# microcontroller.net
KiCad netlist of a schematic drawn in Altium Designer
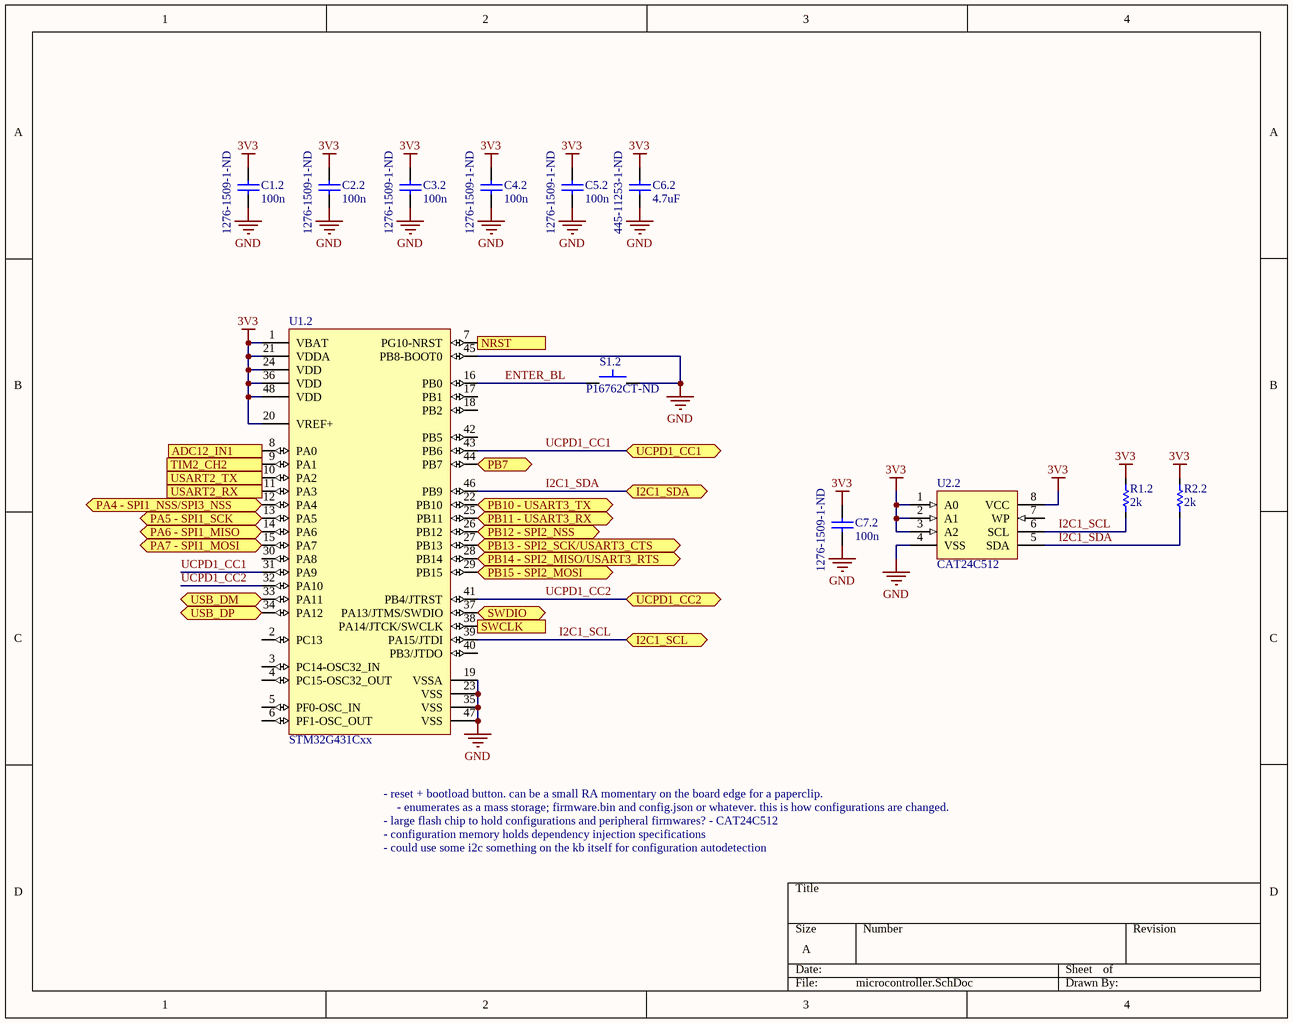
[diagram p0: microcontroller.SchDoc]

(export (version "E")
  (design (tool "Eeschema 10.0.6"))
  (components
    (comp (ref "C1.2")
      (value "100n")
      (footprint "0402")
      (fields (field (name "SUPPLIER PART NUMBER 1") "1276-1509-1-ND"))
      (libsource (lib "Luminaire") (part "CAPACITOR NON_POL"))
    )
    (comp (ref "C2.2")
      (value "100n")
      (footprint "0402")
      (fields (field (name "SUPPLIER PART NUMBER 1") "1276-1509-1-ND"))
      (libsource (lib "Luminaire") (part "CAPACITOR NON_POL"))
    )
    (comp (ref "C3.2")
      (value "100n")
      (footprint "0402")
      (fields (field (name "SUPPLIER PART NUMBER 1") "1276-1509-1-ND"))
      (libsource (lib "Luminaire") (part "CAPACITOR NON_POL"))
    )
    (comp (ref "C4.2")
      (value "100n")
      (footprint "0402")
      (fields (field (name "SUPPLIER PART NUMBER 1") "1276-1509-1-ND"))
      (libsource (lib "Luminaire") (part "CAPACITOR NON_POL"))
    )
    (comp (ref "C5.2")
      (value "100n")
      (footprint "0402")
      (fields (field (name "SUPPLIER PART NUMBER 1") "1276-1509-1-ND"))
      (libsource (lib "Luminaire") (part "CAPACITOR NON_POL"))
    )
    (comp (ref "C6.2")
      (value "4.7uF")
      (footprint "1608[0603]")
      (fields (field (name "SUPPLIER PART NUMBER 1") "445-11253-1-ND"))
      (libsource (lib "KEMET Chip Capacitor") (part "C0402"))
    )
    (comp (ref "C7.2")
      (value "100n")
      (footprint "0402")
      (fields (field (name "SUPPLIER PART NUMBER 1") "1276-1509-1-ND"))
      (libsource (lib "Luminaire") (part "CAPACITOR NON_POL"))
    )
    (comp (ref "R1.2")
      (value "2k")
      (footprint "0402")
      (fields
        (field (name "MANUFACTURER") "Yageo")
        (field (name "MANUFACTURER PART NUMBER") "RC0402JR-072KL")
        (field (name "TOLERANCE") "±5%")
      )
      (libsource (lib "Luminaire") (part "RESISTOR"))
    )
    (comp (ref "R2.2")
      (value "2k")
      (footprint "0402")
      (fields
        (field (name "MANUFACTURER") "Yageo")
        (field (name "MANUFACTURER PART NUMBER") "RC0402JR-072KL")
        (field (name "TOLERANCE") "±5%")
      )
      (libsource (lib "Luminaire") (part "RESISTOR"))
    )
    (comp (ref "S1.2")
      (value "MOM_SWITCH")
      (footprint "EVQ-P6D/P")
      (description "Momentary switch")
      (fields (field (name "SUPPLIER PART NUMBER 1") "P16762CT-ND"))
      (libsource (lib "pokey") (part "MOM_SWITCH"))
    )
    (comp (ref "U1.2")
      (value "STM32G431Cxx")
      (footprint "TSQFP50P900X900X160-48N")
      (libsource (lib "pokey") (part "STM32G431Cxx"))
    )
    (comp (ref "U2.2")
      (value "CAT24C512")
      (footprint "TSOP65P640X120-8N")
      (libsource (lib "pokey") (part "CAT24C512"))
    )
  )
  (nets
    (net (code "1") (name "/ADC12_IN1") (class "Default")
      (node (ref "U1.2") (pin "8") (pinfunction "PA0_8") (pintype "bidirectional"))
    )
    (net (code "2") (name "/ENTER_BL") (class "Default")
      (node (ref "S1.2") (pin "1") (pinfunction "1_1") (pintype "passive"))
      (node (ref "U1.2") (pin "16") (pinfunction "PB0_16") (pintype "bidirectional"))
    )
    (net (code "3") (name "/I2C1_SCL") (class "Default")
      (node (ref "R1.2") (pin "1") (pinfunction "1_1") (pintype "passive"))
      (node (ref "U1.2") (pin "39") (pinfunction "PA15/JTDI_39") (pintype "bidirectional"))
      (node (ref "U2.2") (pin "6") (pinfunction "SCL_6") (pintype "open_collector"))
    )
    (net (code "4") (name "/I2C1_SDA") (class "Default")
      (node (ref "R2.2") (pin "1") (pinfunction "1_1") (pintype "passive"))
      (node (ref "U1.2") (pin "46") (pinfunction "PB9_46") (pintype "bidirectional"))
      (node (ref "U2.2") (pin "5") (pinfunction "SDA_5") (pintype "open_collector"))
    )
    (net (code "6") (name "/NRST") (class "Default")
      (node (ref "U1.2") (pin "7") (pinfunction "PG10-NRST_7") (pintype "bidirectional"))
    )
    (net (code "7") (name "/PA4 - SPI1_NSS{slash}SPI3_NSS") (class "Default")
      (node (ref "U1.2") (pin "12") (pinfunction "PA4_12") (pintype "bidirectional"))
    )
    (net (code "8") (name "/PA5 - SPI1_SCK") (class "Default")
      (node (ref "U1.2") (pin "13") (pinfunction "PA5_13") (pintype "bidirectional"))
    )
    (net (code "9") (name "/PA6 - SPI1_MISO") (class "Default")
      (node (ref "U1.2") (pin "14") (pinfunction "PA6_14") (pintype "bidirectional"))
    )
    (net (code "19") (name "/PA7 - SPI1_MOSI") (class "Default")
      (node (ref "U1.2") (pin "15") (pinfunction "PA7_15") (pintype "bidirectional"))
    )
    (net (code "20") (name "/PB7") (class "Default")
      (node (ref "U1.2") (pin "44") (pinfunction "PB7_44") (pintype "bidirectional"))
    )
    (net (code "21") (name "/PB10 - USART3_TX") (class "Default")
      (node (ref "U1.2") (pin "22") (pinfunction "PB10_22") (pintype "bidirectional"))
    )
    (net (code "22") (name "/PB11 - USART3_RX") (class "Default")
      (node (ref "U1.2") (pin "25") (pinfunction "PB11_25") (pintype "bidirectional"))
    )
    (net (code "23") (name "/PB12 - SPI2_NSS") (class "Default")
      (node (ref "U1.2") (pin "26") (pinfunction "PB12_26") (pintype "bidirectional"))
    )
    (net (code "24") (name "/PB13 - SPI2_SCK{slash}USART3_CTS") (class "Default")
      (node (ref "U1.2") (pin "27") (pinfunction "PB13_27") (pintype "bidirectional"))
    )
    (net (code "25") (name "/PB14 - SPI2_MISO{slash}USART3_RTS") (class "Default")
      (node (ref "U1.2") (pin "28") (pinfunction "PB14_28") (pintype "bidirectional"))
    )
    (net (code "26") (name "/PB15 - SPI2_MOSI") (class "Default")
      (node (ref "U1.2") (pin "29") (pinfunction "PB15_29") (pintype "bidirectional"))
    )
    (net (code "27") (name "/SWCLK") (class "Default")
      (node (ref "U1.2") (pin "38") (pinfunction "PA14/JTCK/SWCLK_38") (pintype "bidirectional"))
    )
    (net (code "28") (name "/SWDIO") (class "Default")
      (node (ref "U1.2") (pin "37") (pinfunction "PA13/JTMS/SWDIO_37") (pintype "bidirectional"))
    )
    (net (code "29") (name "/TIM2_CH2") (class "Default")
      (node (ref "U1.2") (pin "9") (pinfunction "PA1_9") (pintype "bidirectional"))
    )
    (net (code "30") (name "/UCPD1_CC1") (class "Default")
      (node (ref "U1.2") (pin "31") (pinfunction "PA9_31") (pintype "bidirectional"))
      (node (ref "U1.2") (pin "43") (pinfunction "PB6_43") (pintype "bidirectional"))
    )
    (net (code "31") (name "/UCPD1_CC2") (class "Default")
      (node (ref "U1.2") (pin "32") (pinfunction "PA10_32") (pintype "bidirectional"))
      (node (ref "U1.2") (pin "41") (pinfunction "PB4/JTRST_41") (pintype "bidirectional"))
    )
    (net (code "32") (name "/USART2_RX") (class "Default")
      (node (ref "U1.2") (pin "11") (pinfunction "PA3_11") (pintype "bidirectional"))
    )
    (net (code "33") (name "/USART2_TX") (class "Default")
      (node (ref "U1.2") (pin "10") (pinfunction "PA2_10") (pintype "bidirectional"))
    )
    (net (code "34") (name "/USB_DM") (class "Default")
      (node (ref "U1.2") (pin "33") (pinfunction "PA11_33") (pintype "bidirectional"))
    )
    (net (code "35") (name "/USB_DP") (class "Default")
      (node (ref "U1.2") (pin "34") (pinfunction "PA12_34") (pintype "bidirectional"))
    )
    (net (code "36") (name "3V3") (class "Default")
      (node (ref "C1.2") (pin "1") (pinfunction "1_1") (pintype "passive"))
      (node (ref "C2.2") (pin "1") (pinfunction "1_1") (pintype "passive"))
      (node (ref "C3.2") (pin "1") (pinfunction "1_1") (pintype "passive"))
      (node (ref "C4.2") (pin "1") (pinfunction "1_1") (pintype "passive"))
      (node (ref "C5.2") (pin "1") (pinfunction "1_1") (pintype "passive"))
      (node (ref "C6.2") (pin "2") (pinfunction "2_2") (pintype "passive"))
      (node (ref "C7.2") (pin "1") (pinfunction "1_1") (pintype "passive"))
      (node (ref "R1.2") (pin "2") (pinfunction "2_2") (pintype "passive"))
      (node (ref "R2.2") (pin "2") (pinfunction "2_2") (pintype "passive"))
      (node (ref "U1.2") (pin "1") (pinfunction "VBAT_1") (pintype "power_in"))
      (node (ref "U1.2") (pin "20") (pinfunction "VREF+_20") (pintype "power_in"))
      (node (ref "U1.2") (pin "21") (pinfunction "VDDA_21") (pintype "power_in"))
      (node (ref "U1.2") (pin "24") (pinfunction "VDD_24") (pintype "power_in"))
      (node (ref "U1.2") (pin "36") (pinfunction "VDD_36") (pintype "power_in"))
      (node (ref "U1.2") (pin "48") (pinfunction "VDD_48") (pintype "power_in"))
      (node (ref "U2.2") (pin "1") (pinfunction "A0_1") (pintype "input"))
      (node (ref "U2.2") (pin "2") (pinfunction "A1_2") (pintype "input"))
      (node (ref "U2.2") (pin "3") (pinfunction "A2_3") (pintype "input"))
      (node (ref "U2.2") (pin "8") (pinfunction "VCC_8") (pintype "power_in"))
    )
    (net (code "37") (name "GND") (class "Default")
      (node (ref "C1.2") (pin "2") (pinfunction "2_2") (pintype "passive"))
      (node (ref "C2.2") (pin "2") (pinfunction "2_2") (pintype "passive"))
      (node (ref "C3.2") (pin "2") (pinfunction "2_2") (pintype "passive"))
      (node (ref "C4.2") (pin "2") (pinfunction "2_2") (pintype "passive"))
      (node (ref "C5.2") (pin "2") (pinfunction "2_2") (pintype "passive"))
      (node (ref "C6.2") (pin "1") (pinfunction "1_1") (pintype "passive"))
      (node (ref "C7.2") (pin "2") (pinfunction "2_2") (pintype "passive"))
      (node (ref "S1.2") (pin "2") (pinfunction "2_2") (pintype "passive"))
      (node (ref "U1.2") (pin "19") (pinfunction "VSSA_19") (pintype "power_in"))
      (node (ref "U1.2") (pin "23") (pinfunction "VSS_23") (pintype "power_in"))
      (node (ref "U1.2") (pin "35") (pinfunction "VSS_35") (pintype "power_in"))
      (node (ref "U1.2") (pin "45") (pinfunction "PB8-BOOT0_45") (pintype "bidirectional"))
      (node (ref "U1.2") (pin "47") (pinfunction "VSS_47") (pintype "power_in"))
      (node (ref "U2.2") (pin "4") (pinfunction "VSS_4") (pintype "power_in"))
    )
    (net (code "38") (name "unconnected-(U1.2-PA8-Pad30)") (class "Default")
      (node (ref "U1.2") (pin "30") (pinfunction "PA8_30") (pintype "bidirectional"))
    )
    (net (code "39") (name "unconnected-(U1.2-PB1-Pad17)") (class "Default")
      (node (ref "U1.2") (pin "17") (pinfunction "PB1_17") (pintype "bidirectional"))
    )
    (net (code "40") (name "unconnected-(U1.2-PB2-Pad18)") (class "Default")
      (node (ref "U1.2") (pin "18") (pinfunction "PB2_18") (pintype "bidirectional"))
    )
    (net (code "41") (name "unconnected-(U1.2-PB3{slash}JTDO-Pad40)") (class "Default")
      (node (ref "U1.2") (pin "40") (pinfunction "PB3/JTDO_40") (pintype "bidirectional"))
    )
    (net (code "42") (name "unconnected-(U1.2-PB5-Pad42)") (class "Default")
      (node (ref "U1.2") (pin "42") (pinfunction "PB5_42") (pintype "bidirectional"))
    )
    (net (code "43") (name "unconnected-(U1.2-PC13-Pad2)") (class "Default")
      (node (ref "U1.2") (pin "2") (pinfunction "PC13_2") (pintype "bidirectional"))
    )
    (net (code "44") (name "unconnected-(U1.2-PC14-OSC32_IN-Pad3)") (class "Default")
      (node (ref "U1.2") (pin "3") (pinfunction "PC14-OSC32_IN_3") (pintype "bidirectional"))
    )
    (net (code "45") (name "unconnected-(U1.2-PC15-OSC32_OUT-Pad4)") (class "Default")
      (node (ref "U1.2") (pin "4") (pinfunction "PC15-OSC32_OUT_4") (pintype "bidirectional"))
    )
    (net (code "46") (name "unconnected-(U1.2-PF0-OSC_IN-Pad5)") (class "Default")
      (node (ref "U1.2") (pin "5") (pinfunction "PF0-OSC_IN_5") (pintype "bidirectional"))
    )
    (net (code "47") (name "unconnected-(U1.2-PF1-OSC_OUT-Pad6)") (class "Default")
      (node (ref "U1.2") (pin "6") (pinfunction "PF1-OSC_OUT_6") (pintype "bidirectional"))
    )
    (net (code "48") (name "unconnected-(U2.2-WP-Pad7)") (class "Default")
      (node (ref "U2.2") (pin "7") (pinfunction "WP_7") (pintype "input"))
    )
  )
)
